# ft232rl_breakout.net
KiCad netlist of a schematic drawn in EAGLE
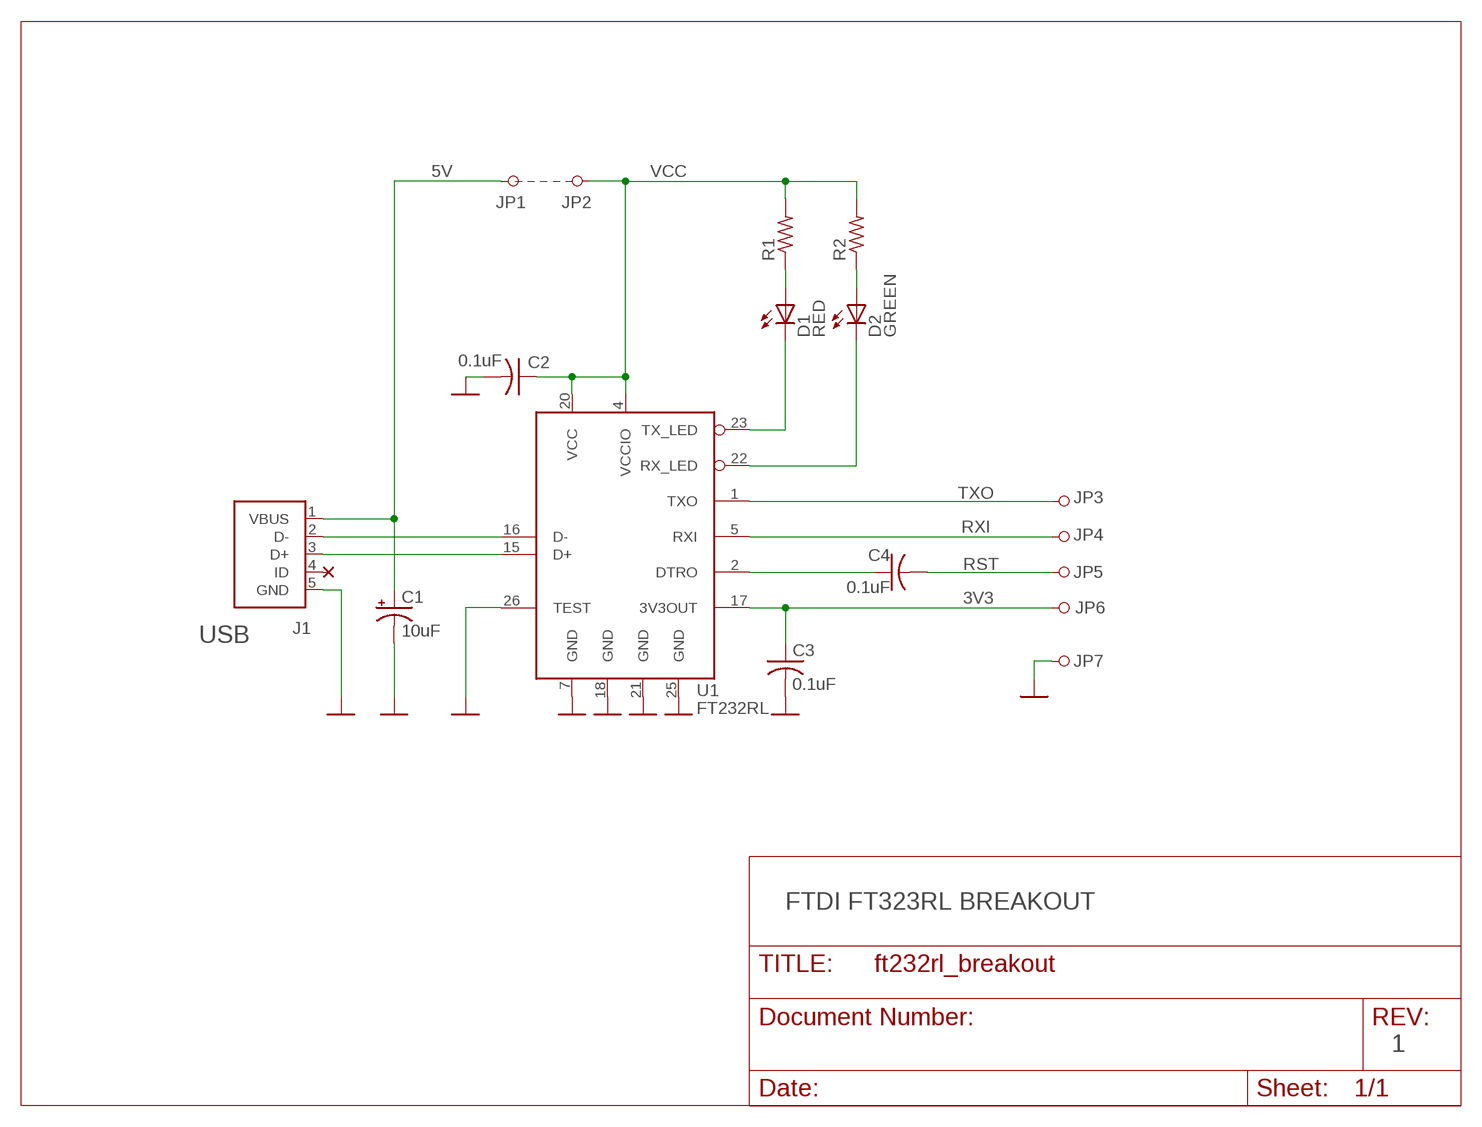
[diagram p0: schematic, sheet 1]

(export (version "E")
  (design (tool "Eeschema 10.0.6"))
  (components
    (comp (ref "C1")
      (value "10uF")
      (footprint "eagle-import:A_3216-18R")
      (libsource (lib "eagle-import") (part "CPOL-USA/3216-18R"))
    )
    (comp (ref "C2")
      (value "0.1uF")
      (footprint "eagle-import:C0402K")
      (libsource (lib "eagle-import") (part "C-USC0402K"))
    )
    (comp (ref "C3")
      (value "0.1uF")
      (footprint "eagle-import:C0402K")
      (libsource (lib "eagle-import") (part "C-USC0402K"))
    )
    (comp (ref "C4")
      (value "0.1uF")
      (footprint "eagle-import:C0402K")
      (libsource (lib "eagle-import") (part "C-USC0402K"))
    )
    (comp (ref "D1")
      (value "RED")
      (footprint "eagle-import:LED_0402")
      (libsource (lib "eagle-import") (part "LED"))
    )
    (comp (ref "D2")
      (value "GREEN")
      (footprint "eagle-import:LED_0402")
      (libsource (lib "eagle-import") (part "LED"))
    )
    (comp (ref "J1")
      (value "USB")
      (footprint "eagle-import:USB-MICRO-ZX62RD-AB-5P8")
      (libsource (lib "eagle-import") (part "USB"))
    )
    (comp (ref "JP1")
      (value "PINHD-1X1")
      (footprint "eagle-import:1X01")
      (libsource (lib "eagle-import") (part "PINHD-1X1"))
    )
    (comp (ref "JP2")
      (value "PINHD-1X1")
      (footprint "eagle-import:1X01")
      (libsource (lib "eagle-import") (part "PINHD-1X1"))
    )
    (comp (ref "JP3")
      (value "PINHD-1X1")
      (footprint "eagle-import:1X01")
      (libsource (lib "eagle-import") (part "PINHD-1X1"))
    )
    (comp (ref "JP4")
      (value "PINHD-1X1")
      (footprint "eagle-import:1X01")
      (libsource (lib "eagle-import") (part "PINHD-1X1"))
    )
    (comp (ref "JP5")
      (value "PINHD-1X1")
      (footprint "eagle-import:1X01")
      (libsource (lib "eagle-import") (part "PINHD-1X1"))
    )
    (comp (ref "JP6")
      (value "PINHD-1X1")
      (footprint "eagle-import:1X01")
      (libsource (lib "eagle-import") (part "PINHD-1X1"))
    )
    (comp (ref "JP7")
      (value "PINHD-1X1")
      (footprint "eagle-import:1X01")
      (libsource (lib "eagle-import") (part "PINHD-1X1"))
    )
    (comp (ref "R1")
      (value "R-US_R0402")
      (footprint "eagle-import:R0402")
      (libsource (lib "eagle-import") (part "R-US_R0402"))
    )
    (comp (ref "R2")
      (value "R-US_R0402")
      (footprint "eagle-import:R0402")
      (libsource (lib "eagle-import") (part "R-US_R0402"))
    )
    (comp (ref "U1")
      (value "FT232RL")
      (footprint "eagle-import:SSOP28DB")
      (libsource (lib "eagle-import") (part "FT232RL"))
    )
  )
  (nets
    (net (code "1") (name "/3V3") (class "Default")
      (node (ref "C3") (pin "1") (pinfunction "1_1") (pintype "passive"))
      (node (ref "JP6") (pin "1") (pinfunction "1_1") (pintype "passive"))
      (node (ref "U1") (pin "17") (pinfunction "3V3OUT_17") (pintype "power_in"))
    )
    (net (code "2") (name "/5V") (class "Default")
      (node (ref "C1") (pin "+") (pinfunction "+_+") (pintype "passive"))
      (node (ref "J1") (pin "1") (pinfunction "VBUS_1") (pintype "bidirectional"))
      (node (ref "JP1") (pin "1") (pinfunction "1_1") (pintype "passive"))
    )
    (net (code "3") (name "/RST") (class "Default")
      (node (ref "C4") (pin "2") (pinfunction "2_2") (pintype "passive"))
      (node (ref "JP5") (pin "1") (pinfunction "1_1") (pintype "passive"))
    )
    (net (code "4") (name "/RXI") (class "Default")
      (node (ref "JP4") (pin "1") (pinfunction "1_1") (pintype "passive"))
      (node (ref "U1") (pin "5") (pinfunction "RXI_5") (pintype "input"))
    )
    (net (code "5") (name "/TXO") (class "Default")
      (node (ref "JP3") (pin "1") (pinfunction "1_1") (pintype "passive"))
      (node (ref "U1") (pin "1") (pinfunction "TXO_1") (pintype "output"))
    )
    (net (code "6") (name "/VCC") (class "Default")
      (node (ref "C2") (pin "1") (pinfunction "1_1") (pintype "passive"))
      (node (ref "JP2") (pin "1") (pinfunction "1_1") (pintype "passive"))
      (node (ref "R1") (pin "2") (pinfunction "2_2") (pintype "passive"))
      (node (ref "R2") (pin "2") (pinfunction "2_2") (pintype "passive"))
      (node (ref "U1") (pin "20") (pinfunction "VCC_20") (pintype "power_in"))
      (node (ref "U1") (pin "4") (pinfunction "VCCIO_4") (pintype "power_in"))
    )
    (net (code "7") (name "GND") (class "Default")
      (node (ref "C1") (pin "-") (pinfunction "-_-") (pintype "passive"))
      (node (ref "C2") (pin "2") (pinfunction "2_2") (pintype "passive"))
      (node (ref "C3") (pin "2") (pinfunction "2_2") (pintype "passive"))
      (node (ref "J1") (pin "5") (pinfunction "GND_5") (pintype "bidirectional"))
      (node (ref "JP7") (pin "1") (pinfunction "1_1") (pintype "passive"))
      (node (ref "U1") (pin "18") (pinfunction "GND_18") (pintype "power_in"))
      (node (ref "U1") (pin "21") (pinfunction "GND_21") (pintype "power_in"))
      (node (ref "U1") (pin "25") (pinfunction "GND_25") (pintype "power_in"))
      (node (ref "U1") (pin "26") (pinfunction "TEST_26") (pintype "input"))
      (node (ref "U1") (pin "7") (pinfunction "GND_7") (pintype "power_in"))
    )
    (net (code "8") (name "Net-(D1-PadA)") (class "Default")
      (node (ref "D1") (pin "A") (pinfunction "A_A") (pintype "passive"))
      (node (ref "R1") (pin "1") (pinfunction "1_1") (pintype "passive"))
    )
    (net (code "9") (name "Net-(D2-PadA)") (class "Default")
      (node (ref "D2") (pin "A") (pinfunction "A_A") (pintype "passive"))
      (node (ref "R2") (pin "1") (pinfunction "1_1") (pintype "passive"))
    )
    (net (code "10") (name "Net-(J1-D+)") (class "Default")
      (node (ref "J1") (pin "3") (pinfunction "D+_3") (pintype "bidirectional"))
      (node (ref "U1") (pin "15") (pinfunction "D+_15") (pintype "passive"))
    )
    (net (code "11") (name "Net-(J1-D-)") (class "Default")
      (node (ref "J1") (pin "2") (pinfunction "D-_2") (pintype "bidirectional"))
      (node (ref "U1") (pin "16") (pinfunction "D-_16") (pintype "passive"))
    )
    (net (code "12") (name "Net-(U1-DTRO)") (class "Default")
      (node (ref "C4") (pin "1") (pinfunction "1_1") (pintype "passive"))
      (node (ref "U1") (pin "2") (pinfunction "DTRO_2") (pintype "output"))
    )
    (net (code "13") (name "Net-(U1-RX_LED)") (class "Default")
      (node (ref "D2") (pin "C") (pinfunction "C_C") (pintype "passive"))
      (node (ref "U1") (pin "22") (pinfunction "RX_LED_22") (pintype "output"))
    )
    (net (code "14") (name "Net-(U1-TX_LED)") (class "Default")
      (node (ref "D1") (pin "C") (pinfunction "C_C") (pintype "passive"))
      (node (ref "U1") (pin "23") (pinfunction "TX_LED_23") (pintype "output"))
    )
    (net (code "15") (name "unconnected-(J1-ID-Pad4)") (class "Default")
      (node (ref "J1") (pin "4") (pinfunction "ID_4") (pintype "bidirectional"))
    )
  )
)
